# PCB_Telemetria_2020.net
KiCad netlist of a schematic drawn in EAGLE
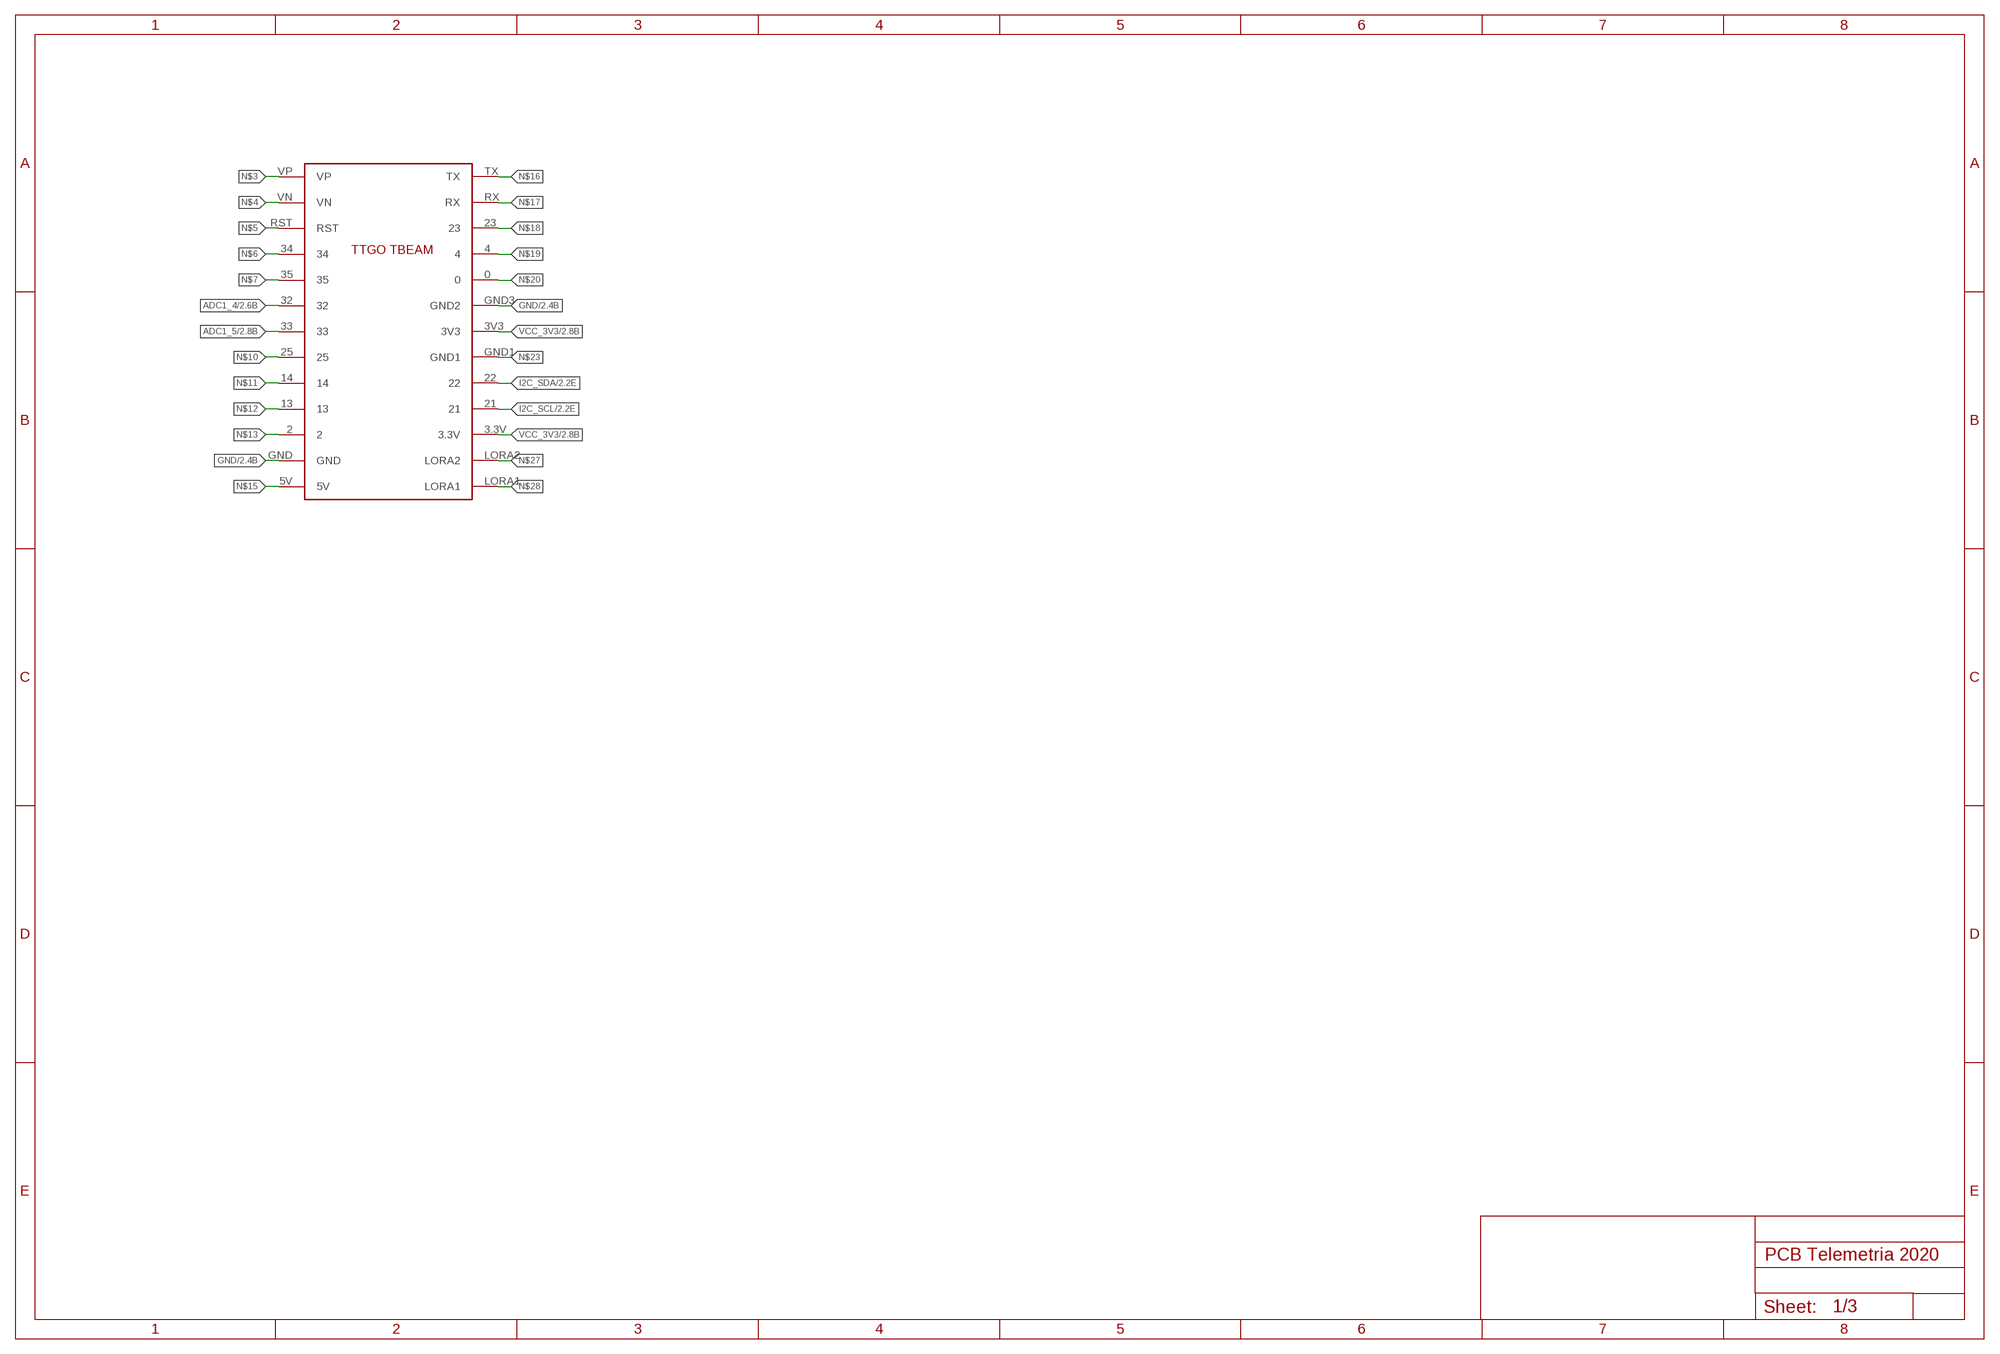
[diagram p0: schematic, sheet 1]
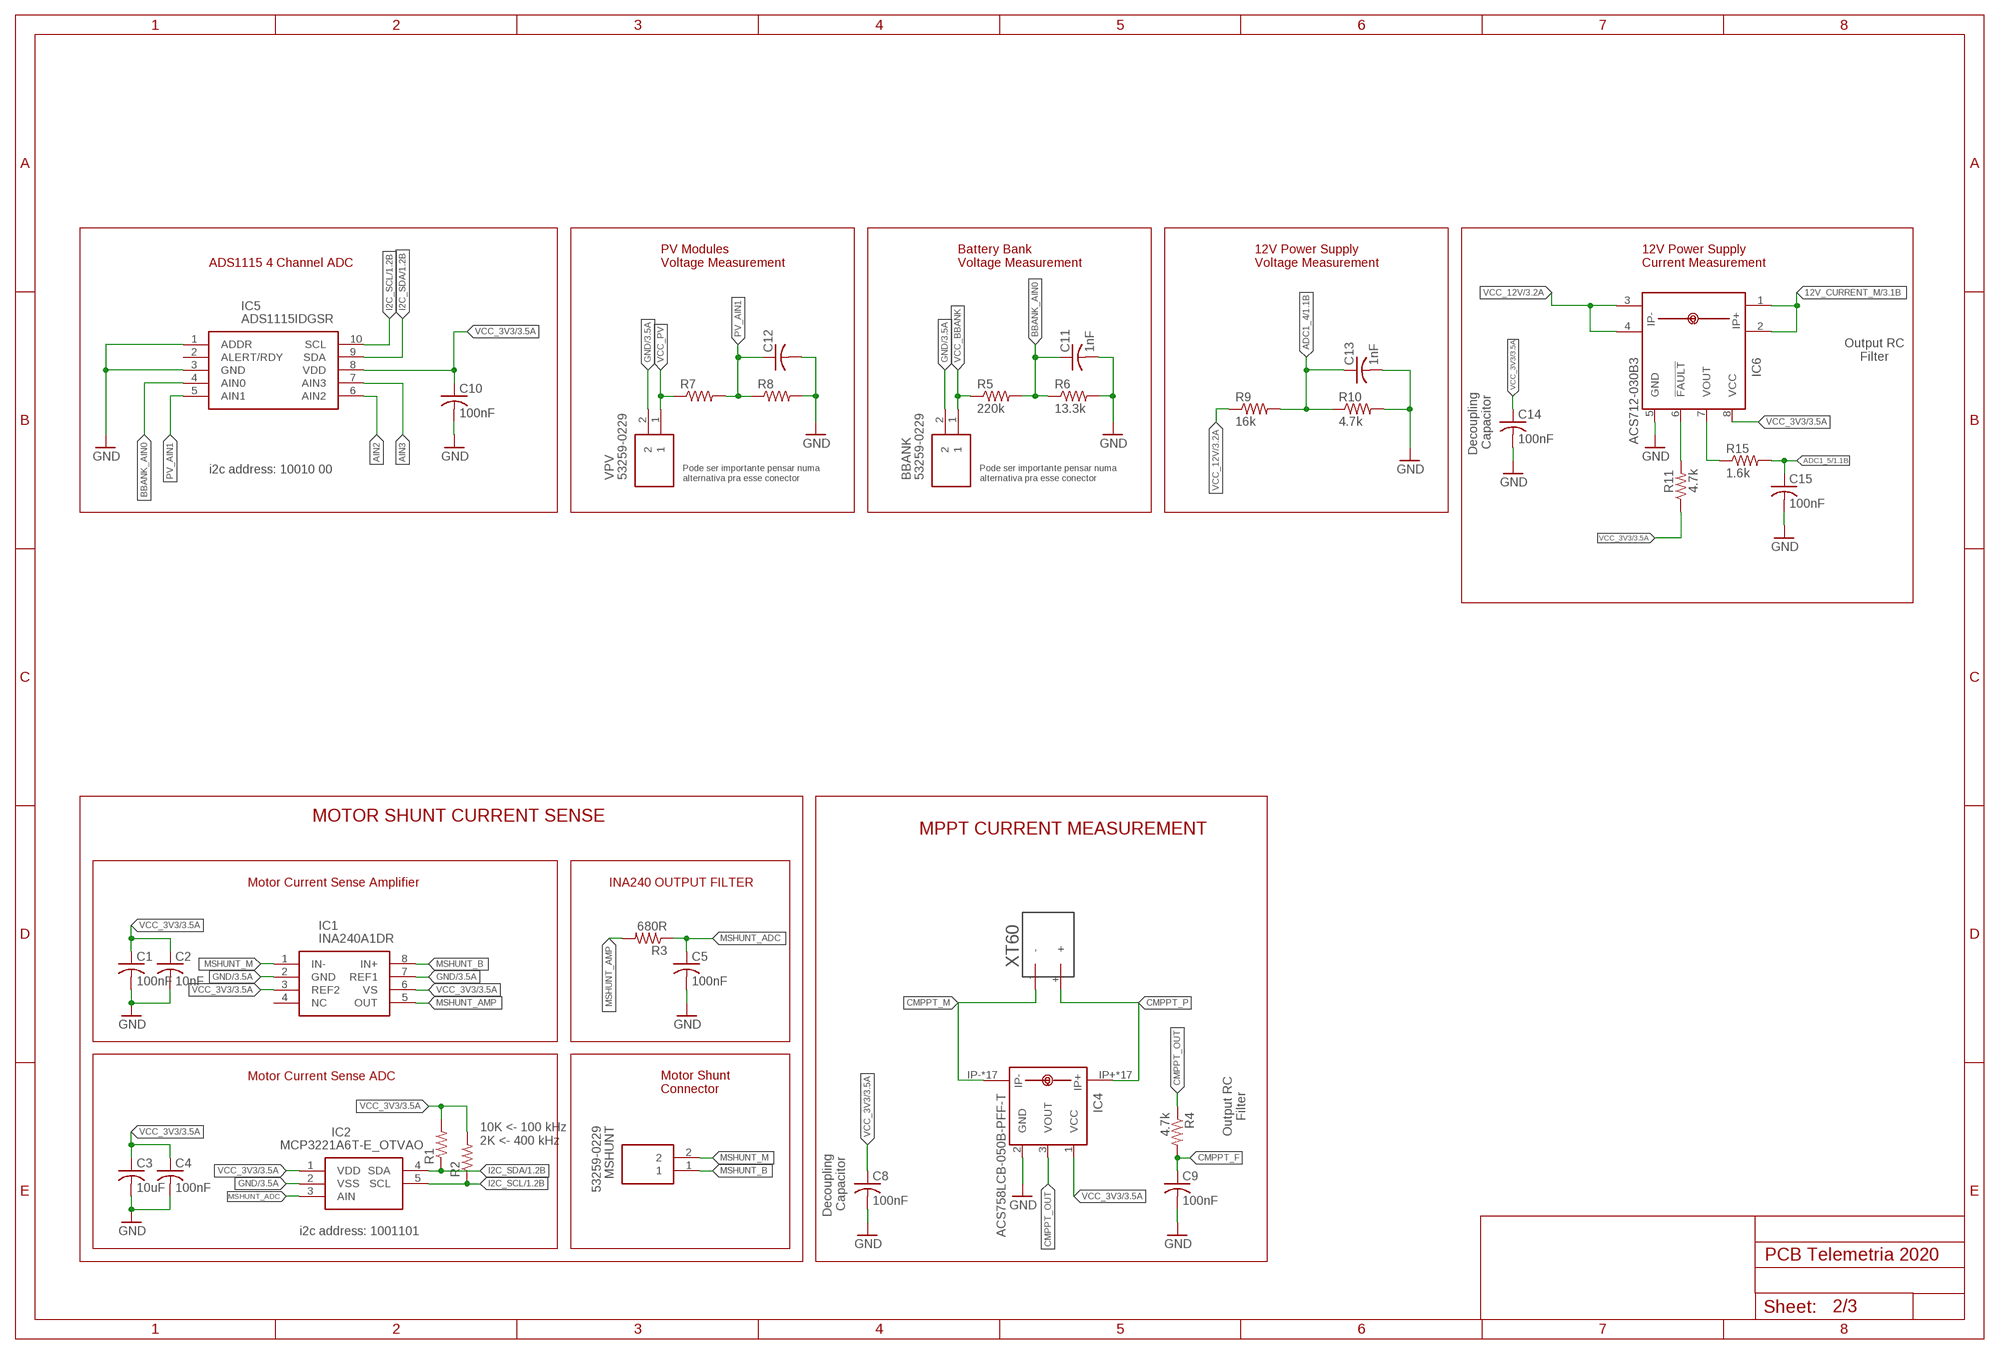
[diagram p1: schematic, sheet 2]
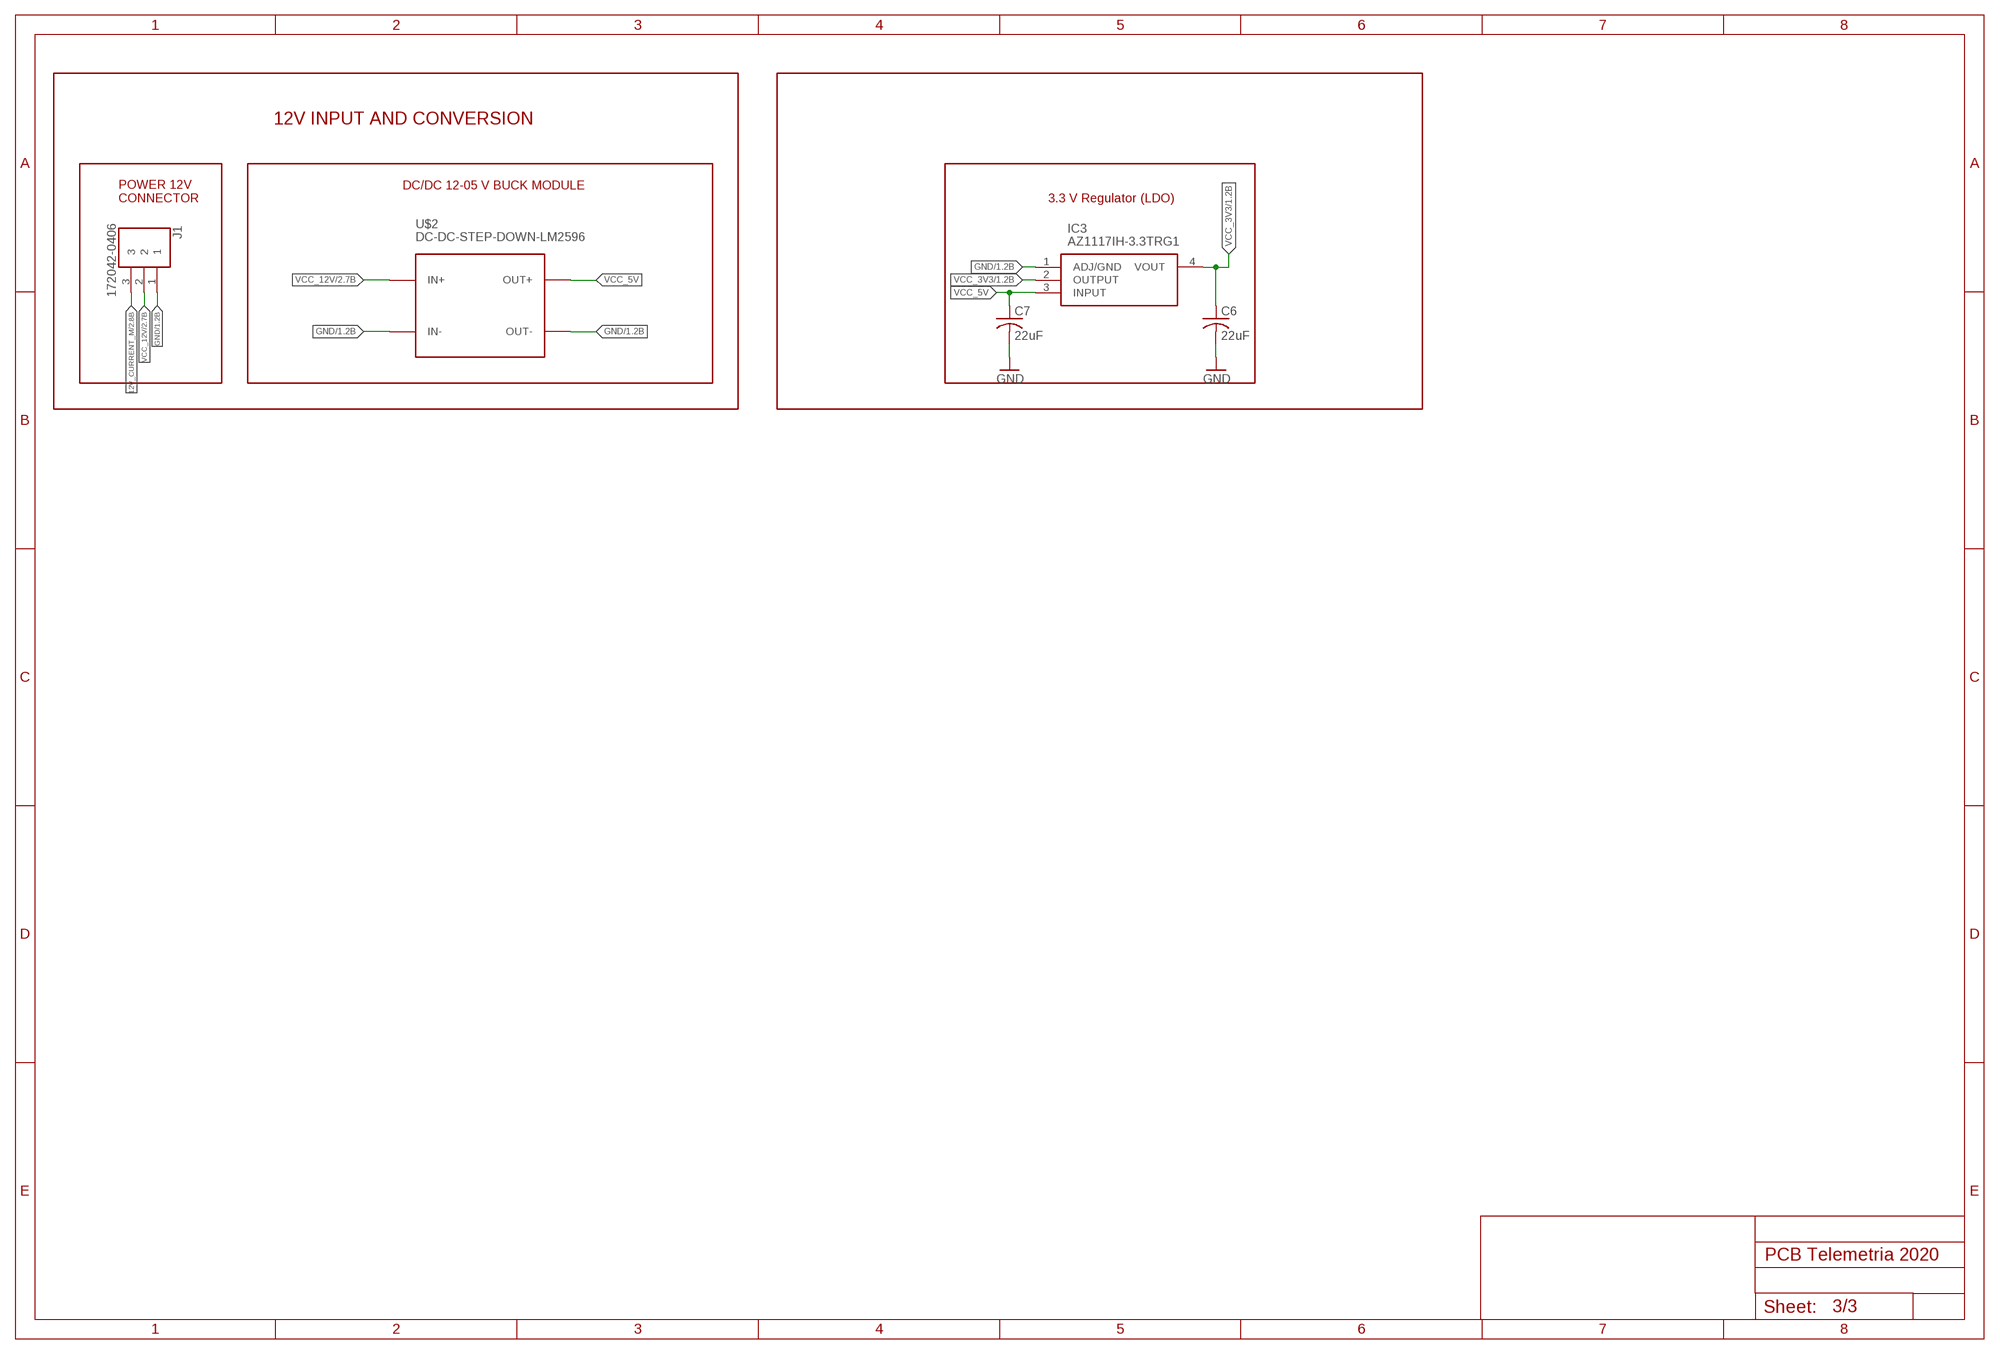
[diagram p2: schematic, sheet 3]

(export (version "E")
  (design (tool "Eeschema 10.0.6"))
  (components
    (comp (ref "U$1")
      (value "TTGOBEAM")
      (footprint "eagle-import:TTGOBEAM")
      (libsource (lib "eagle-import") (part "TTGOBEAM"))
    )
    (comp (ref "BBANK")
      (value "53259-0229")
      (footprint "eagle-import:0532590229")
      (fields (field (name "MOUSER_PART_NUMBER") "538-53259-0229"))
      (libsource (lib "eagle-import") (part "53259-0229"))
    )
    (comp (ref "C1")
      (value "100nF")
      (footprint "eagle-import:C0805")
      (libsource (lib "eagle-import") (part "C-USC0805"))
    )
    (comp (ref "C2")
      (value "10nF")
      (footprint "eagle-import:C0805")
      (libsource (lib "eagle-import") (part "C-USC0805"))
    )
    (comp (ref "C3")
      (value "10uF")
      (footprint "eagle-import:C0805")
      (libsource (lib "eagle-import") (part "C-USC0805"))
    )
    (comp (ref "C4")
      (value "100nF")
      (footprint "eagle-import:C0805")
      (libsource (lib "eagle-import") (part "C-USC0805"))
    )
    (comp (ref "C5")
      (value "100nF")
      (footprint "eagle-import:C0805")
      (libsource (lib "eagle-import") (part "C-USC0805"))
    )
    (comp (ref "C8")
      (value "100nF")
      (footprint "eagle-import:C0805")
      (libsource (lib "eagle-import") (part "C-USC0805"))
    )
    (comp (ref "C9")
      (value "100nF")
      (footprint "eagle-import:C0805")
      (libsource (lib "eagle-import") (part "C-USC0805"))
    )
    (comp (ref "C10")
      (value "100nF")
      (footprint "eagle-import:C0805")
      (libsource (lib "eagle-import") (part "C-USC0805"))
    )
    (comp (ref "C11")
      (value "1nF")
      (footprint "eagle-import:C0805")
      (libsource (lib "eagle-import") (part "C-USC0805"))
    )
    (comp (ref "C12")
      (value "C-USC0805")
      (footprint "eagle-import:C0805")
      (libsource (lib "eagle-import") (part "C-USC0805"))
    )
    (comp (ref "C13")
      (value "1nF")
      (footprint "eagle-import:C0805")
      (libsource (lib "eagle-import") (part "C-USC0805"))
    )
    (comp (ref "C14")
      (value "100nF")
      (footprint "eagle-import:C0805")
      (libsource (lib "eagle-import") (part "C-USC0805"))
    )
    (comp (ref "C15")
      (value "100nF")
      (footprint "eagle-import:C0805")
      (libsource (lib "eagle-import") (part "C-USC0805"))
    )
    (comp (ref "IC1")
      (value "INA240A1DR")
      (footprint "eagle-import:SOIC127P600X175-8N")
      (fields (field (name "MOUSER_PART_NUMBER") "595-INA240A1DR"))
      (libsource (lib "eagle-import") (part "INA240A1DR"))
    )
    (comp (ref "IC2")
      (value "MCP3221A6T-E_OTVAO")
      (footprint "eagle-import:SOT95P280X145-5N")
      (fields
        (field (name "MANUFACTURER_PART_NUMBER") "MCP3221A6T-E/OTVAO")
        (field (name "MOUSER_PART_NUMBER") "579-MCP3221A6TEOTVAO")
      )
      (libsource (lib "eagle-import") (part "MCP3221A6T-E_OTVAO"))
    )
    (comp (ref "IC4")
      (value "ACS758LCB-050B-PFF-T")
      (footprint "eagle-import:CB-PFF")
      (libsource (lib "eagle-import") (part "ACS758LCB-050B-PFF-T"))
    )
    (comp (ref "IC5")
      (value "ADS1115IDGSR")
      (footprint "eagle-import:SOP50P490X110-10N")
      (fields (field (name "MOUSER_PART_NUMBER") "595-ADS1115IDGSR"))
      (libsource (lib "eagle-import") (part "ADS1115IDGSR"))
    )
    (comp (ref "IC6")
      (value "ACS712-030B3")
      (footprint "eagle-import:SOIC8")
      (libsource (lib "eagle-import") (part "ACS712-LC"))
    )
    (comp (ref "MSHUNT")
      (value "53259-0229")
      (footprint "eagle-import:0532590229")
      (fields (field (name "MOUSER_PART_NUMBER") "538-53259-0229"))
      (libsource (lib "eagle-import") (part "53259-0229"))
    )
    (comp (ref "R1")
      (value "R-US_R0805")
      (footprint "eagle-import:R0805")
      (libsource (lib "eagle-import") (part "R-US_R0805"))
    )
    (comp (ref "R2")
      (value "R-US_R0805")
      (footprint "eagle-import:R0805")
      (libsource (lib "eagle-import") (part "R-US_R0805"))
    )
    (comp (ref "R3")
      (value "680R")
      (footprint "eagle-import:R0805")
      (libsource (lib "eagle-import") (part "R-US_R0805"))
    )
    (comp (ref "R4")
      (value "4.7k")
      (footprint "eagle-import:R0805")
      (libsource (lib "eagle-import") (part "R-US_R0805"))
    )
    (comp (ref "R5")
      (value "220k")
      (footprint "eagle-import:R0805")
      (libsource (lib "eagle-import") (part "R-US_R0805"))
    )
    (comp (ref "R6")
      (value "13.3k")
      (footprint "eagle-import:R0805")
      (libsource (lib "eagle-import") (part "R-US_R0805"))
    )
    (comp (ref "R7")
      (value "R-US_R0805")
      (footprint "eagle-import:R0805")
      (libsource (lib "eagle-import") (part "R-US_R0805"))
    )
    (comp (ref "R8")
      (value "R-US_R0805")
      (footprint "eagle-import:R0805")
      (libsource (lib "eagle-import") (part "R-US_R0805"))
    )
    (comp (ref "R9")
      (value "16k")
      (footprint "eagle-import:R0805")
      (libsource (lib "eagle-import") (part "R-US_R0805"))
    )
    (comp (ref "R10")
      (value "4.7k")
      (footprint "eagle-import:R0805")
      (libsource (lib "eagle-import") (part "R-US_R0805"))
    )
    (comp (ref "R11")
      (value "4.7k")
      (footprint "eagle-import:R0805")
      (libsource (lib "eagle-import") (part "R-US_R0805"))
    )
    (comp (ref "R15")
      (value "1.6k")
      (footprint "eagle-import:R0805")
      (libsource (lib "eagle-import") (part "R-US_R0805"))
    )
    (comp (ref "U$3")
      (value "XT60")
      (footprint "eagle-import:XT60")
      (libsource (lib "eagle-import") (part "XT60"))
    )
    (comp (ref "VPV")
      (value "53259-0229")
      (footprint "eagle-import:0532590229")
      (fields (field (name "MOUSER_PART_NUMBER") "538-53259-0229"))
      (libsource (lib "eagle-import") (part "53259-0229"))
    )
    (comp (ref "C6")
      (value "22uF")
      (footprint "eagle-import:C0805")
      (libsource (lib "eagle-import") (part "C-USC0805"))
    )
    (comp (ref "C7")
      (value "22uF")
      (footprint "eagle-import:C0805")
      (libsource (lib "eagle-import") (part "C-USC0805"))
    )
    (comp (ref "IC3")
      (value "AZ1117IH-3.3TRG1")
      (footprint "eagle-import:SOT230P700X170-4N")
      (fields (field (name "MOUSER_PART_NUMBER") "621-AZ1117IH-3.3TRG1"))
      (libsource (lib "eagle-import") (part "AZ1117IH-3.3TRG1"))
    )
    (comp (ref "J1")
      (value "172042-0406")
      (footprint "eagle-import:MOLEX_172042-0406")
      (fields (field (name "MF") "Molex") (field (name "MP") "172042-0302"))
      (libsource (lib "eagle-import") (part "172042-0406"))
    )
    (comp (ref "U$2")
      (value "DC-DC-STEP-DOWN-LM2596")
      (footprint "eagle-import:DC-DC-STEP-DOWN-LM2596")
      (libsource (lib "eagle-import") (part "DC-DC-STEP-DOWN-LM2596"))
    )
  )
  (nets
    (net (code "1") (name "12V_CURRENT_M") (class "Default")
      (node (ref "IC6") (pin "1") (pinfunction "IP+_1") (pintype "passive"))
      (node (ref "IC6") (pin "2") (pinfunction "IP+1_2") (pintype "passive"))
      (node (ref "J1") (pin "3") (pinfunction "3_3") (pintype "passive"))
    )
    (net (code "2") (name "ADC1_4") (class "Default")
      (node (ref "C13") (pin "1") (pinfunction "1_1") (pintype "passive"))
      (node (ref "R10") (pin "1") (pinfunction "1_1") (pintype "passive"))
      (node (ref "R9") (pin "2") (pinfunction "2_2") (pintype "passive"))
      (node (ref "U$1") (pin "32") (pinfunction "32_32") (pintype "bidirectional"))
    )
    (net (code "3") (name "ADC1_5") (class "Default")
      (node (ref "C15") (pin "1") (pinfunction "1_1") (pintype "passive"))
      (node (ref "R15") (pin "2") (pinfunction "2_2") (pintype "passive"))
      (node (ref "U$1") (pin "33") (pinfunction "33_33") (pintype "bidirectional"))
    )
    (net (code "4") (name "AIN2") (class "Default")
      (node (ref "IC5") (pin "6") (pinfunction "AIN2_6") (pintype "bidirectional"))
    )
    (net (code "5") (name "AIN3") (class "Default")
      (node (ref "IC5") (pin "7") (pinfunction "AIN3_7") (pintype "bidirectional"))
    )
    (net (code "6") (name "BBANK_AIN0") (class "Default")
      (node (ref "C11") (pin "1") (pinfunction "1_1") (pintype "passive"))
      (node (ref "IC5") (pin "4") (pinfunction "AIN0_4") (pintype "bidirectional"))
      (node (ref "R5") (pin "2") (pinfunction "2_2") (pintype "passive"))
      (node (ref "R6") (pin "1") (pinfunction "1_1") (pintype "passive"))
    )
    (net (code "7") (name "CMPPT_F") (class "Default")
      (node (ref "C9") (pin "1") (pinfunction "1_1") (pintype "passive"))
      (node (ref "R4") (pin "2") (pinfunction "2_2") (pintype "passive"))
    )
    (net (code "8") (name "CMPPT_M") (class "Default")
      (node (ref "IC4") (pin "IP-") (pinfunction "IP-_IP-") (pintype "passive"))
      (node (ref "IC4") (pin "IP-@10") (pinfunction "IP-_IP-@10") (pintype "passive"))
      (node (ref "IC4") (pin "IP-@11") (pinfunction "IP-_IP-@11") (pintype "passive"))
      (node (ref "IC4") (pin "IP-@12") (pinfunction "IP-_IP-@12") (pintype "passive"))
      (node (ref "IC4") (pin "IP-@13") (pinfunction "IP-_IP-@13") (pintype "passive"))
      (node (ref "IC4") (pin "IP-@14") (pinfunction "IP-_IP-@14") (pintype "passive"))
      (node (ref "IC4") (pin "IP-@15") (pinfunction "IP-_IP-@15") (pintype "passive"))
      (node (ref "IC4") (pin "IP-@16") (pinfunction "IP-_IP-@16") (pintype "passive"))
      (node (ref "IC4") (pin "IP-@17") (pinfunction "IP-_IP-@17") (pintype "passive"))
      (node (ref "IC4") (pin "IP-@2") (pinfunction "IP-_IP-@2") (pintype "passive"))
      (node (ref "IC4") (pin "IP-@3") (pinfunction "IP-_IP-@3") (pintype "passive"))
      (node (ref "IC4") (pin "IP-@4") (pinfunction "IP-_IP-@4") (pintype "passive"))
      (node (ref "IC4") (pin "IP-@5") (pinfunction "IP-_IP-@5") (pintype "passive"))
      (node (ref "IC4") (pin "IP-@6") (pinfunction "IP-_IP-@6") (pintype "passive"))
      (node (ref "IC4") (pin "IP-@7") (pinfunction "IP-_IP-@7") (pintype "passive"))
      (node (ref "IC4") (pin "IP-@8") (pinfunction "IP-_IP-@8") (pintype "passive"))
      (node (ref "IC4") (pin "IP-@9") (pinfunction "IP-_IP-@9") (pintype "passive"))
      (node (ref "U$3") (pin "-") (pinfunction "-_-") (pintype "bidirectional"))
    )
    (net (code "9") (name "CMPPT_OUT") (class "Default")
      (node (ref "IC4") (pin "3") (pinfunction "VOUT_3") (pintype "output"))
      (node (ref "R4") (pin "1") (pinfunction "1_1") (pintype "passive"))
    )
    (net (code "10") (name "CMPPT_P") (class "Default")
      (node (ref "IC4") (pin "IP+") (pinfunction "IP+_IP+") (pintype "passive"))
      (node (ref "IC4") (pin "IP+@10") (pinfunction "IP+_IP+@10") (pintype "passive"))
      (node (ref "IC4") (pin "IP+@11") (pinfunction "IP+_IP+@11") (pintype "passive"))
      (node (ref "IC4") (pin "IP+@12") (pinfunction "IP+_IP+@12") (pintype "passive"))
      (node (ref "IC4") (pin "IP+@13") (pinfunction "IP+_IP+@13") (pintype "passive"))
      (node (ref "IC4") (pin "IP+@14") (pinfunction "IP+_IP+@14") (pintype "passive"))
      (node (ref "IC4") (pin "IP+@15") (pinfunction "IP+_IP+@15") (pintype "passive"))
      (node (ref "IC4") (pin "IP+@16") (pinfunction "IP+_IP+@16") (pintype "passive"))
      (node (ref "IC4") (pin "IP+@17") (pinfunction "IP+_IP+@17") (pintype "passive"))
      (node (ref "IC4") (pin "IP+@2") (pinfunction "IP+_IP+@2") (pintype "passive"))
      (node (ref "IC4") (pin "IP+@3") (pinfunction "IP+_IP+@3") (pintype "passive"))
      (node (ref "IC4") (pin "IP+@4") (pinfunction "IP+_IP+@4") (pintype "passive"))
      (node (ref "IC4") (pin "IP+@5") (pinfunction "IP+_IP+@5") (pintype "passive"))
      (node (ref "IC4") (pin "IP+@6") (pinfunction "IP+_IP+@6") (pintype "passive"))
      (node (ref "IC4") (pin "IP+@7") (pinfunction "IP+_IP+@7") (pintype "passive"))
      (node (ref "IC4") (pin "IP+@8") (pinfunction "IP+_IP+@8") (pintype "passive"))
      (node (ref "IC4") (pin "IP+@9") (pinfunction "IP+_IP+@9") (pintype "passive"))
      (node (ref "U$3") (pin "+") (pinfunction "+_+") (pintype "bidirectional"))
    )
    (net (code "11") (name "GND") (class "Default")
      (node (ref "BBANK") (pin "2") (pinfunction "2_2") (pintype "bidirectional"))
      (node (ref "C1") (pin "2") (pinfunction "2_2") (pintype "passive"))
      (node (ref "C10") (pin "2") (pinfunction "2_2") (pintype "passive"))
      (node (ref "C11") (pin "2") (pinfunction "2_2") (pintype "passive"))
      (node (ref "C12") (pin "2") (pinfunction "2_2") (pintype "passive"))
      (node (ref "C13") (pin "2") (pinfunction "2_2") (pintype "passive"))
      (node (ref "C14") (pin "2") (pinfunction "2_2") (pintype "passive"))
      (node (ref "C15") (pin "2") (pinfunction "2_2") (pintype "passive"))
      (node (ref "C2") (pin "2") (pinfunction "2_2") (pintype "passive"))
      (node (ref "C3") (pin "2") (pinfunction "2_2") (pintype "passive"))
      (node (ref "C4") (pin "2") (pinfunction "2_2") (pintype "passive"))
      (node (ref "C5") (pin "2") (pinfunction "2_2") (pintype "passive"))
      (node (ref "C6") (pin "2") (pinfunction "2_2") (pintype "passive"))
      (node (ref "C7") (pin "2") (pinfunction "2_2") (pintype "passive"))
      (node (ref "C8") (pin "2") (pinfunction "2_2") (pintype "passive"))
      (node (ref "C9") (pin "2") (pinfunction "2_2") (pintype "passive"))
      (node (ref "IC1") (pin "2") (pinfunction "GND_2") (pintype "bidirectional"))
      (node (ref "IC1") (pin "7") (pinfunction "REF1_7") (pintype "bidirectional"))
      (node (ref "IC2") (pin "2") (pinfunction "VSS_2") (pintype "bidirectional"))
      (node (ref "IC3") (pin "1") (pinfunction "ADJ/GND_1") (pintype "bidirectional"))
      (node (ref "IC4") (pin "2") (pinfunction "GND_2") (pintype "power_in"))
      (node (ref "IC5") (pin "1") (pinfunction "ADDR_1") (pintype "bidirectional"))
      (node (ref "IC5") (pin "3") (pinfunction "GND_3") (pintype "bidirectional"))
      (node (ref "IC6") (pin "5") (pinfunction "GND_5") (pintype "power_in"))
      (node (ref "J1") (pin "1") (pinfunction "1_1") (pintype "passive"))
      (node (ref "R10") (pin "2") (pinfunction "2_2") (pintype "passive"))
      (node (ref "R6") (pin "2") (pinfunction "2_2") (pintype "passive"))
      (node (ref "R8") (pin "2") (pinfunction "2_2") (pintype "passive"))
      (node (ref "U$1") (pin "GND") (pinfunction "GND_GND") (pintype "bidirectional"))
      (node (ref "U$1") (pin "GND3") (pinfunction "GND2_GND3") (pintype "bidirectional"))
      (node (ref "U$2") (pin "IN-") (pinfunction "IN-_IN-") (pintype "bidirectional"))
      (node (ref "U$2") (pin "OUT-") (pinfunction "OUT-_OUT-") (pintype "bidirectional"))
      (node (ref "VPV") (pin "2") (pinfunction "2_2") (pintype "bidirectional"))
    )
    (net (code "12") (name "I2C_SCL") (class "Default")
      (node (ref "IC2") (pin "5") (pinfunction "SCL_5") (pintype "bidirectional"))
      (node (ref "IC5") (pin "10") (pinfunction "SCL_10") (pintype "bidirectional"))
      (node (ref "R2") (pin "1") (pinfunction "1_1") (pintype "passive"))
      (node (ref "U$1") (pin "21") (pinfunction "21_21") (pintype "bidirectional"))
    )
    (net (code "13") (name "I2C_SDA") (class "Default")
      (node (ref "IC2") (pin "4") (pinfunction "SDA_4") (pintype "bidirectional"))
      (node (ref "IC5") (pin "9") (pinfunction "SDA_9") (pintype "bidirectional"))
      (node (ref "R1") (pin "1") (pinfunction "1_1") (pintype "passive"))
      (node (ref "U$1") (pin "22") (pinfunction "22_22") (pintype "bidirectional"))
    )
    (net (code "14") (name "MSHUNT_ADC") (class "Default")
      (node (ref "C5") (pin "1") (pinfunction "1_1") (pintype "passive"))
      (node (ref "IC2") (pin "3") (pinfunction "AIN_3") (pintype "bidirectional"))
      (node (ref "R3") (pin "1") (pinfunction "1_1") (pintype "passive"))
    )
    (net (code "15") (name "MSHUNT_AMP") (class "Default")
      (node (ref "IC1") (pin "5") (pinfunction "OUT_5") (pintype "bidirectional"))
      (node (ref "R3") (pin "2") (pinfunction "2_2") (pintype "passive"))
    )
    (net (code "16") (name "MSHUNT_B") (class "Default")
      (node (ref "IC1") (pin "8") (pinfunction "IN+_8") (pintype "bidirectional"))
      (node (ref "MSHUNT") (pin "1") (pinfunction "1_1") (pintype "bidirectional"))
    )
    (net (code "17") (name "MSHUNT_M") (class "Default")
      (node (ref "IC1") (pin "1") (pinfunction "IN-_1") (pintype "bidirectional"))
      (node (ref "MSHUNT") (pin "2") (pinfunction "2_2") (pintype "bidirectional"))
    )
    (net (code "18") (name "N$3") (class "Default")
      (node (ref "U$1") (pin "VP") (pinfunction "VP_VP") (pintype "bidirectional"))
    )
    (net (code "19") (name "N$4") (class "Default")
      (node (ref "U$1") (pin "VN") (pinfunction "VN_VN") (pintype "bidirectional"))
    )
    (net (code "20") (name "N$5") (class "Default")
      (node (ref "U$1") (pin "RST") (pinfunction "RST_RST") (pintype "bidirectional"))
    )
    (net (code "21") (name "N$6") (class "Default")
      (node (ref "U$1") (pin "34") (pinfunction "34_34") (pintype "bidirectional"))
    )
    (net (code "22") (name "N$7") (class "Default")
      (node (ref "U$1") (pin "35") (pinfunction "35_35") (pintype "bidirectional"))
    )
    (net (code "23") (name "N$10") (class "Default")
      (node (ref "U$1") (pin "25") (pinfunction "25_25") (pintype "bidirectional"))
    )
    (net (code "24") (name "N$11") (class "Default")
      (node (ref "U$1") (pin "14") (pinfunction "14_14") (pintype "bidirectional"))
    )
    (net (code "25") (name "N$12") (class "Default")
      (node (ref "U$1") (pin "13") (pinfunction "13_13") (pintype "bidirectional"))
    )
    (net (code "26") (name "N$13") (class "Default")
      (node (ref "U$1") (pin "2") (pinfunction "2_2") (pintype "bidirectional"))
    )
    (net (code "27") (name "N$15") (class "Default")
      (node (ref "U$1") (pin "5V") (pinfunction "5V_5V") (pintype "bidirectional"))
    )
    (net (code "28") (name "N$16") (class "Default")
      (node (ref "U$1") (pin "TX") (pinfunction "TX_TX") (pintype "bidirectional"))
    )
    (net (code "29") (name "N$17") (class "Default")
      (node (ref "U$1") (pin "RX") (pinfunction "RX_RX") (pintype "bidirectional"))
    )
    (net (code "30") (name "N$18") (class "Default")
      (node (ref "U$1") (pin "23") (pinfunction "23_23") (pintype "bidirectional"))
    )
    (net (code "31") (name "N$19") (class "Default")
      (node (ref "U$1") (pin "4") (pinfunction "4_4") (pintype "bidirectional"))
    )
    (net (code "32") (name "N$20") (class "Default")
      (node (ref "U$1") (pin "0") (pinfunction "0_0") (pintype "bidirectional"))
    )
    (net (code "33") (name "N$23") (class "Default")
      (node (ref "U$1") (pin "GND1") (pinfunction "GND1_GND1") (pintype "bidirectional"))
    )
    (net (code "34") (name "N$27") (class "Default")
      (node (ref "U$1") (pin "LORA2") (pinfunction "LORA2_LORA2") (pintype "bidirectional"))
    )
    (net (code "35") (name "N$28") (class "Default")
      (node (ref "U$1") (pin "LORA1") (pinfunction "LORA1_LORA1") (pintype "bidirectional"))
    )
    (net (code "36") (name "Net-(IC6-VOUT)") (class "Default")
      (node (ref "IC6") (pin "7") (pinfunction "VOUT_7") (pintype "output"))
      (node (ref "R15") (pin "1") (pinfunction "1_1") (pintype "passive"))
    )
    (net (code "37") (name "Net-(IC6-~{FAULT})") (class "Default")
      (node (ref "IC6") (pin "6") (pinfunction "~{FAULT}_6") (pintype "bidirectional"))
      (node (ref "R11") (pin "2") (pinfunction "2_2") (pintype "passive"))
    )
    (net (code "38") (name "PV_AIN1") (class "Default")
      (node (ref "C12") (pin "1") (pinfunction "1_1") (pintype "passive"))
      (node (ref "IC5") (pin "5") (pinfunction "AIN1_5") (pintype "bidirectional"))
      (node (ref "R7") (pin "2") (pinfunction "2_2") (pintype "passive"))
      (node (ref "R8") (pin "1") (pinfunction "1_1") (pintype "passive"))
    )
    (net (code "39") (name "VCC_3V3") (class "Default")
      (node (ref "C1") (pin "1") (pinfunction "1_1") (pintype "passive"))
      (node (ref "C10") (pin "1") (pinfunction "1_1") (pintype "passive"))
      (node (ref "C14") (pin "1") (pinfunction "1_1") (pintype "passive"))
      (node (ref "C2") (pin "1") (pinfunction "1_1") (pintype "passive"))
      (node (ref "C3") (pin "1") (pinfunction "1_1") (pintype "passive"))
      (node (ref "C4") (pin "1") (pinfunction "1_1") (pintype "passive"))
      (node (ref "C6") (pin "1") (pinfunction "1_1") (pintype "passive"))
      (node (ref "C8") (pin "1") (pinfunction "1_1") (pintype "passive"))
      (node (ref "IC1") (pin "3") (pinfunction "REF2_3") (pintype "bidirectional"))
      (node (ref "IC1") (pin "6") (pinfunction "VS_6") (pintype "bidirectional"))
      (node (ref "IC2") (pin "1") (pinfunction "VDD_1") (pintype "bidirectional"))
      (node (ref "IC3") (pin "2") (pinfunction "OUTPUT_2") (pintype "bidirectional"))
      (node (ref "IC3") (pin "4") (pinfunction "VOUT_4") (pintype "bidirectional"))
      (node (ref "IC4") (pin "1") (pinfunction "VCC_1") (pintype "power_in"))
      (node (ref "IC5") (pin "8") (pinfunction "VDD_8") (pintype "bidirectional"))
      (node (ref "IC6") (pin "8") (pinfunction "VCC_8") (pintype "power_in"))
      (node (ref "R1") (pin "2") (pinfunction "2_2") (pintype "passive"))
      (node (ref "R11") (pin "1") (pinfunction "1_1") (pintype "passive"))
      (node (ref "R2") (pin "2") (pinfunction "2_2") (pintype "passive"))
      (node (ref "U$1") (pin "3.3V") (pinfunction "3.3V_3.3V") (pintype "bidirectional"))
      (node (ref "U$1") (pin "3V3") (pinfunction "3V3_3V3") (pintype "bidirectional"))
    )
    (net (code "40") (name "VCC_5V") (class "Default")
      (node (ref "C7") (pin "1") (pinfunction "1_1") (pintype "passive"))
      (node (ref "IC3") (pin "3") (pinfunction "INPUT_3") (pintype "bidirectional"))
      (node (ref "U$2") (pin "OUT+") (pinfunction "OUT+_OUT+") (pintype "bidirectional"))
    )
    (net (code "41") (name "VCC_12V") (class "Default")
      (node (ref "IC6") (pin "3") (pinfunction "IP-_3") (pintype "passive"))
      (node (ref "IC6") (pin "4") (pinfunction "IP-1_4") (pintype "passive"))
      (node (ref "J1") (pin "2") (pinfunction "2_2") (pintype "passive"))
      (node (ref "R9") (pin "1") (pinfunction "1_1") (pintype "passive"))
      (node (ref "U$2") (pin "IN+") (pinfunction "IN+_IN+") (pintype "bidirectional"))
    )
    (net (code "42") (name "VCC_BBANK") (class "Default")
      (node (ref "BBANK") (pin "1") (pinfunction "1_1") (pintype "bidirectional"))
      (node (ref "R5") (pin "1") (pinfunction "1_1") (pintype "passive"))
    )
    (net (code "43") (name "VCC_PV") (class "Default")
      (node (ref "R7") (pin "1") (pinfunction "1_1") (pintype "passive"))
      (node (ref "VPV") (pin "1") (pinfunction "1_1") (pintype "bidirectional"))
    )
    (net (code "44") (name "unconnected-(IC1-NC-Pad4)") (class "Default")
      (node (ref "IC1") (pin "4") (pinfunction "NC_4") (pintype "no_connect"))
    )
    (net (code "45") (name "unconnected-(IC5-ALERT{slash}RDY-Pad2)") (class "Default")
      (node (ref "IC5") (pin "2") (pinfunction "ALERT/RDY_2") (pintype "bidirectional"))
    )
  )
)
